# BTL-TKHTN-Schematic.net
KiCad netlist of a schematic drawn in Altium Designer
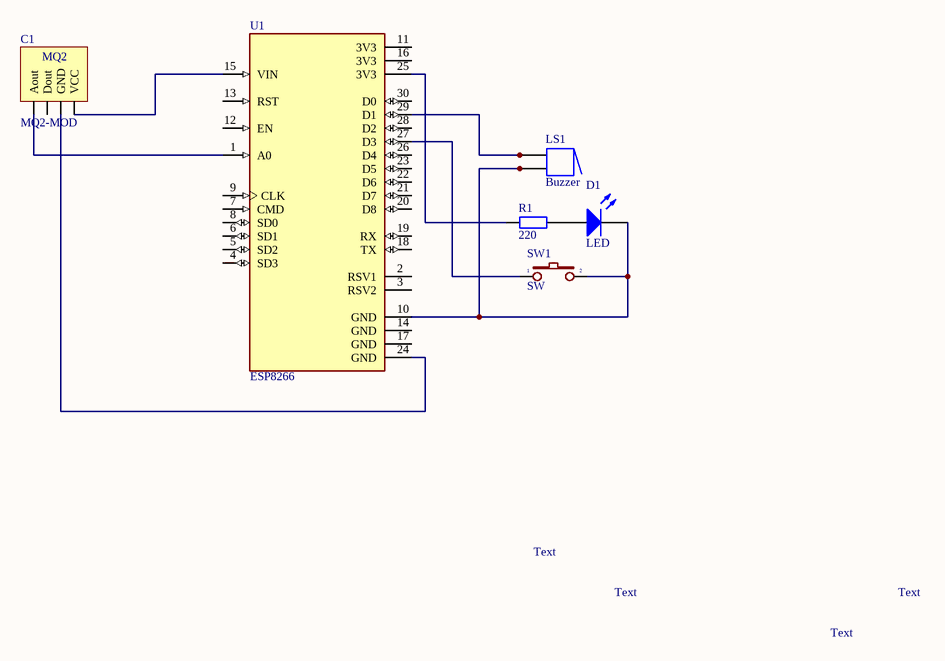
[diagram p0: BTL-TKHTN-Schematic.SchDoc]

(export (version "E")
  (design (tool "Eeschema 10.0.6"))
  (components
    (comp (ref "C1")
      (value "MQ2-MOD")
      (footprint "MQ2-MODULE")
      (fields
        (field (name "MANUFACTURER") "Würth Elektronik eiSos GmbH")
        (field (name "PARTNO") "613004143121")
        (field (name "CREATED BY") "Karrer Zheng")
      )
      (libsource (lib "KhanhBK_SCH_Library_2") (part "MQ2-MOD"))
    )
    (comp (ref "D1")
      (value "LED")
      (footprint "MinhTien_PcbLib:LED_5mm")
      (description "Typical INFRARED GaAs LED")
      (fields (field (name "PUBLISHER") "Altium Limited"))
      (libsource (lib "KhanhBK_SCH_Lib_5") (part "LED"))
    )
    (comp (ref "LS1")
      (value "Buzzer")
      (footprint "ABSM-1574")
      (description "Magnetic Transducer Buzzer")
      (fields (field (name "PUBLISHER") "Altium Limited"))
      (libsource (lib "Miscellaneous Devices") (part "Buzzer"))
    )
    (comp (ref "R1")
      (value "220")
      (footprint "RES-1/4W")
      (description "Resistor R1/4W")
      (libsource (lib "KhanhBK_Library_4") (part "R"))
    )
    (comp (ref "SW1")
      (value "SW")
      (footprint "SW2")
      (description "Switch button 2 pin")
      (libsource (lib "syhaunguyen") (part "SW2"))
    )
    (comp (ref "U1")
      (value "ESP8266")
      (footprint "MODULE_ZC563900")
      (description "NodeMcu Lua ESP8266 WIFI Internet of Things Network Development Module Board")
      (fields (field (name "MF") "YKS") (field (name "MP") "ZC563900"))
      (libsource (lib "ZC563900") (part "ZC563900"))
    )
  )
  (nets
    (net (code "1") (name "Net-(C1-Aout)") (class "Default")
      (node (ref "C1") (pin "1") (pinfunction "Aout_1") (pintype "passive"))
      (node (ref "U1") (pin "1") (pinfunction "A0_1") (pintype "input"))
    )
    (net (code "2") (name "Net-(C1-GND)") (class "Default")
      (node (ref "C1") (pin "3") (pinfunction "GND_3") (pintype "passive"))
      (node (ref "U1") (pin "24") (pinfunction "GND_24") (pintype "power_in"))
    )
    (net (code "3") (name "Net-(C1-VCC)") (class "Default")
      (node (ref "C1") (pin "4") (pinfunction "VCC_4") (pintype "passive"))
      (node (ref "U1") (pin "15") (pinfunction "VIN_15") (pintype "input"))
    )
    (net (code "4") (name "Net-(D1-A)") (class "Default")
      (node (ref "D1") (pin "1") (pinfunction "A_1") (pintype "passive"))
      (node (ref "R1") (pin "2") (pinfunction "2_2") (pintype "passive"))
    )
    (net (code "5") (name "Net-(D1-K)") (class "Default")
      (node (ref "D1") (pin "2") (pinfunction "K_2") (pintype "passive"))
      (node (ref "LS1") (pin "2") (pinfunction "2_2") (pintype "passive"))
      (node (ref "LS1") (pin "2A") (pinfunction "2A_2A") (pintype "passive"))
      (node (ref "SW1") (pin "2") (pinfunction "2_2") (pintype "passive"))
      (node (ref "U1") (pin "10") (pinfunction "GND_10") (pintype "power_in"))
    )
    (net (code "6") (name "Net-(R1-Pad1)") (class "Default")
      (node (ref "R1") (pin "1") (pinfunction "1_1") (pintype "passive"))
      (node (ref "U1") (pin "25") (pinfunction "3V3_25") (pintype "power_in"))
    )
    (net (code "7") (name "Net-(U1-D1)") (class "Default")
      (node (ref "LS1") (pin "1") (pinfunction "1_1") (pintype "passive"))
      (node (ref "LS1") (pin "1A") (pinfunction "1A_1A") (pintype "passive"))
      (node (ref "U1") (pin "29") (pinfunction "D1_29") (pintype "bidirectional"))
    )
    (net (code "8") (name "Net-(U1-D3)") (class "Default")
      (node (ref "SW1") (pin "1") (pinfunction "1_1") (pintype "passive"))
      (node (ref "U1") (pin "27") (pinfunction "D3_27") (pintype "bidirectional"))
    )
    (net (code "9") (name "unconnected-(C1-Dout-Pad2)") (class "Default")
      (node (ref "C1") (pin "2") (pinfunction "Dout_2") (pintype "passive"))
    )
    (net (code "10") (name "unconnected-(U1-3V3-Pad11)") (class "Default")
      (node (ref "U1") (pin "11") (pinfunction "3V3_11") (pintype "power_in"))
    )
    (net (code "11") (name "unconnected-(U1-3V3-Pad16)") (class "Default")
      (node (ref "U1") (pin "16") (pinfunction "3V3_16") (pintype "power_in"))
    )
    (net (code "12") (name "unconnected-(U1-CLK-Pad9)") (class "Default")
      (node (ref "U1") (pin "9") (pinfunction "CLK_9") (pintype "input"))
    )
    (net (code "13") (name "unconnected-(U1-CMD-Pad7)") (class "Default")
      (node (ref "U1") (pin "7") (pinfunction "CMD_7") (pintype "input"))
    )
    (net (code "14") (name "unconnected-(U1-D0-Pad30)") (class "Default")
      (node (ref "U1") (pin "30") (pinfunction "D0_30") (pintype "bidirectional"))
    )
    (net (code "15") (name "unconnected-(U1-D2-Pad28)") (class "Default")
      (node (ref "U1") (pin "28") (pinfunction "D2_28") (pintype "bidirectional"))
    )
    (net (code "16") (name "unconnected-(U1-D4-Pad26)") (class "Default")
      (node (ref "U1") (pin "26") (pinfunction "D4_26") (pintype "bidirectional"))
    )
    (net (code "17") (name "unconnected-(U1-D5-Pad23)") (class "Default")
      (node (ref "U1") (pin "23") (pinfunction "D5_23") (pintype "bidirectional"))
    )
    (net (code "18") (name "unconnected-(U1-D6-Pad22)") (class "Default")
      (node (ref "U1") (pin "22") (pinfunction "D6_22") (pintype "bidirectional"))
    )
    (net (code "19") (name "unconnected-(U1-D7-Pad21)") (class "Default")
      (node (ref "U1") (pin "21") (pinfunction "D7_21") (pintype "bidirectional"))
    )
    (net (code "20") (name "unconnected-(U1-D8-Pad20)") (class "Default")
      (node (ref "U1") (pin "20") (pinfunction "D8_20") (pintype "bidirectional"))
    )
    (net (code "21") (name "unconnected-(U1-EN-Pad12)") (class "Default")
      (node (ref "U1") (pin "12") (pinfunction "EN_12") (pintype "input"))
    )
    (net (code "22") (name "unconnected-(U1-GND-Pad14)") (class "Default")
      (node (ref "U1") (pin "14") (pinfunction "GND_14") (pintype "power_in"))
    )
    (net (code "23") (name "unconnected-(U1-GND-Pad17)") (class "Default")
      (node (ref "U1") (pin "17") (pinfunction "GND_17") (pintype "power_in"))
    )
    (net (code "24") (name "unconnected-(U1-RST-Pad13)") (class "Default")
      (node (ref "U1") (pin "13") (pinfunction "RST_13") (pintype "input"))
    )
    (net (code "25") (name "unconnected-(U1-RSV1-Pad2)") (class "Default")
      (node (ref "U1") (pin "2") (pinfunction "RSV1_2") (pintype "passive"))
    )
    (net (code "26") (name "unconnected-(U1-RSV2-Pad3)") (class "Default")
      (node (ref "U1") (pin "3") (pinfunction "RSV2_3") (pintype "passive"))
    )
    (net (code "27") (name "unconnected-(U1-RX-Pad19)") (class "Default")
      (node (ref "U1") (pin "19") (pinfunction "RX_19") (pintype "bidirectional"))
    )
    (net (code "28") (name "unconnected-(U1-SD0-Pad8)") (class "Default")
      (node (ref "U1") (pin "8") (pinfunction "SD0_8") (pintype "bidirectional"))
    )
    (net (code "29") (name "unconnected-(U1-SD1-Pad6)") (class "Default")
      (node (ref "U1") (pin "6") (pinfunction "SD1_6") (pintype "bidirectional"))
    )
    (net (code "30") (name "unconnected-(U1-SD2-Pad5)") (class "Default")
      (node (ref "U1") (pin "5") (pinfunction "SD2_5") (pintype "bidirectional"))
    )
    (net (code "31") (name "unconnected-(U1-SD3-Pad4)") (class "Default")
      (node (ref "U1") (pin "4") (pinfunction "SD3_4") (pintype "bidirectional"))
    )
    (net (code "32") (name "unconnected-(U1-TX-Pad18)") (class "Default")
      (node (ref "U1") (pin "18") (pinfunction "TX_18") (pintype "bidirectional"))
    )
  )
)
